# CFD_Timing.net
KiCad netlist of a schematic drawn in Altium Designer
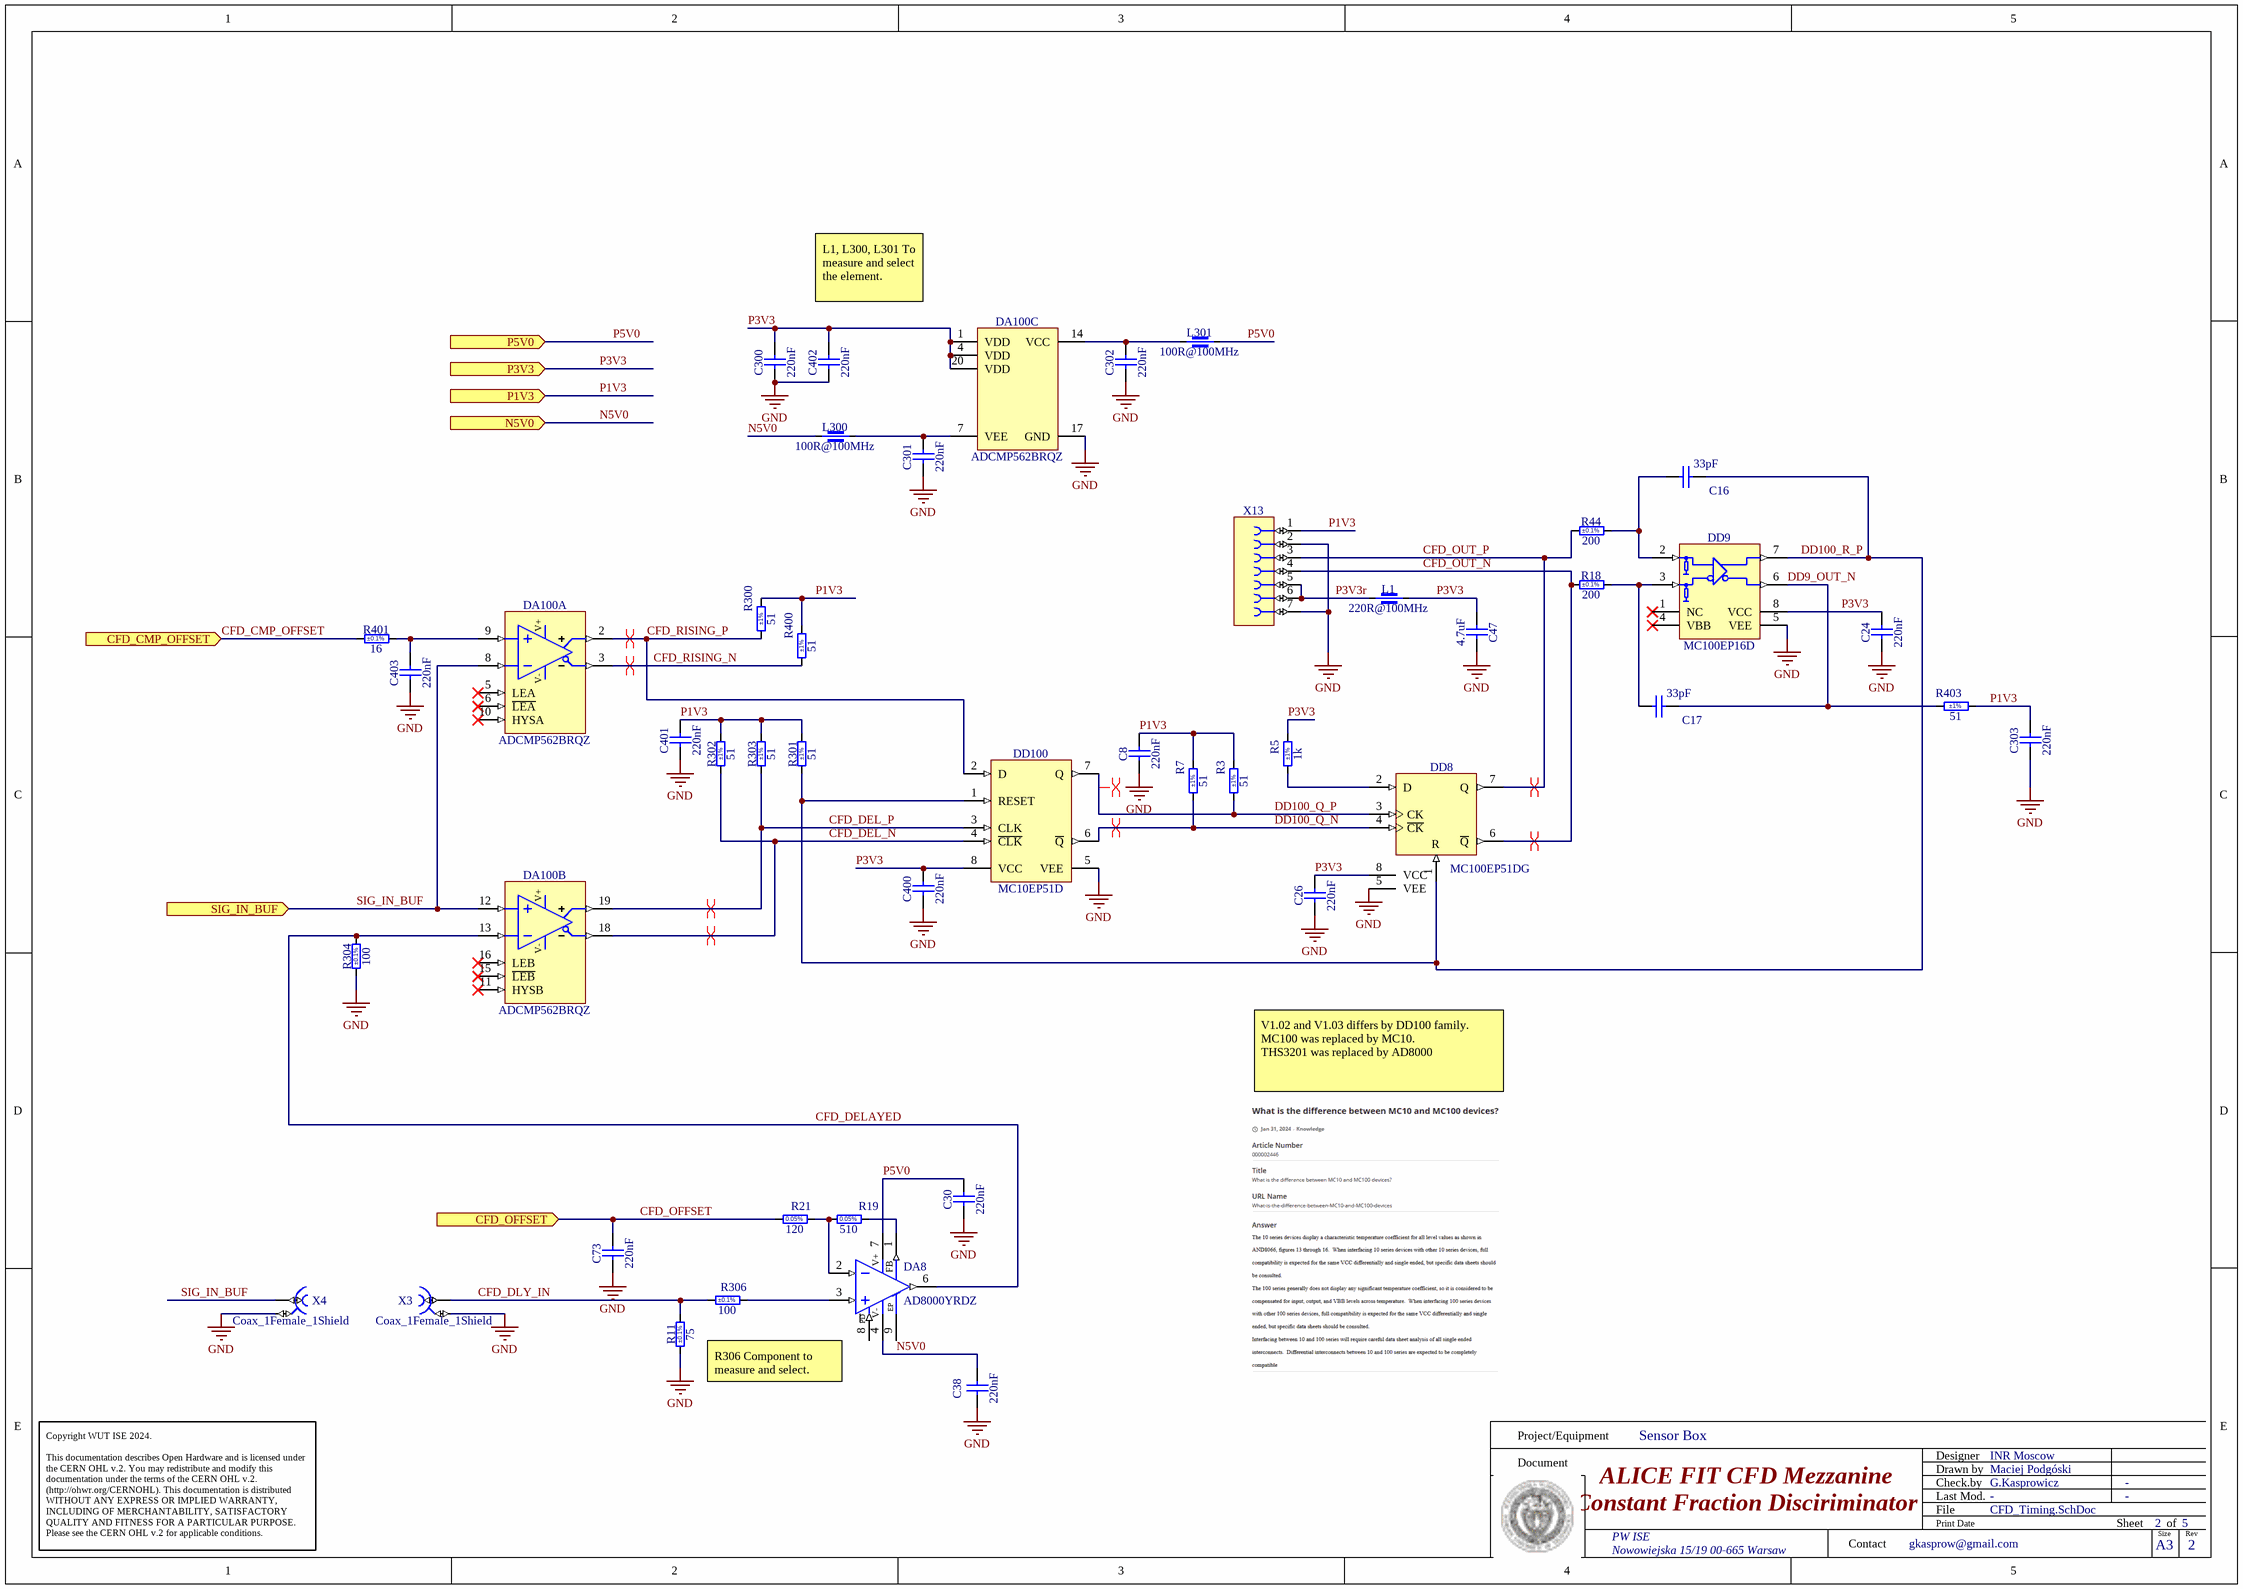
[diagram p0: CFD_Timing.SchDoc]

(export (version "E")
  (design (tool "Eeschema 10.0.6"))
  (components
    (comp (ref "C8")
      (value "220nF")
      (footprint "CAPC2012X135N")
      (description "Non-polarised capacitor")
      (fields
        (field (name "PART NUMBER") "CC0805_220NF_50V_10%_X7R")
        (field (name "VOLTAGE") "50V")
        (field (name "AUTHOR") "CERN DEM JLC")
      )
      (libsource (lib "Capacitors") (part "Capacitor - non polarized"))
    )
    (comp (ref "C16")
      (value "33pF")
      (footprint "CAPC2012X135N")
      (description "Non-polarised capacitor")
      (fields
        (field (name "PART NUMBER") "CC0805_33PF_50V_5%_NP0")
        (field (name "VOLTAGE") "50V")
        (field (name "AUTHOR") "CERN DEM JLC")
      )
      (libsource (lib "Capacitors") (part "Capacitor - non polarized"))
    )
    (comp (ref "C17")
      (value "33pF")
      (footprint "CAPC2012X135N")
      (description "Non-polarised capacitor")
      (fields
        (field (name "PART NUMBER") "CC0805_33PF_50V_5%_NP0")
        (field (name "VOLTAGE") "50V")
        (field (name "AUTHOR") "CERN DEM JLC")
      )
      (libsource (lib "Capacitors") (part "Capacitor - non polarized"))
    )
    (comp (ref "C24")
      (value "220nF")
      (footprint "CAPC2012X135N")
      (description "Non-polarised capacitor")
      (fields
        (field (name "PART NUMBER") "CC0805_220NF_50V_10%_X7R")
        (field (name "VOLTAGE") "50V")
        (field (name "AUTHOR") "CERN DEM JLC")
      )
      (libsource (lib "Capacitors") (part "Capacitor - non polarized"))
    )
    (comp (ref "C26")
      (value "220nF")
      (footprint "CAPC2012X135N")
      (description "Non-polarised capacitor")
      (fields
        (field (name "PART NUMBER") "CC0805_220NF_50V_10%_X7R")
        (field (name "VOLTAGE") "50V")
        (field (name "AUTHOR") "CERN DEM JLC")
      )
      (libsource (lib "Capacitors") (part "Capacitor - non polarized"))
    )
    (comp (ref "C30")
      (value "220nF")
      (footprint "CAPC2012X135N")
      (description "Non-polarised capacitor")
      (fields
        (field (name "PART NUMBER") "CC0805_220NF_50V_10%_X7R")
        (field (name "VOLTAGE") "50V")
        (field (name "AUTHOR") "CERN DEM JLC")
      )
      (libsource (lib "Capacitors") (part "Capacitor - non polarized"))
    )
    (comp (ref "C38")
      (value "220nF")
      (footprint "CAPC2012X135N")
      (description "Non-polarised capacitor")
      (fields
        (field (name "PART NUMBER") "CC0805_220NF_50V_10%_X7R")
        (field (name "VOLTAGE") "50V")
        (field (name "AUTHOR") "CERN DEM JLC")
      )
      (libsource (lib "Capacitors") (part "Capacitor - non polarized"))
    )
    (comp (ref "C47")
      (value "4.7uF")
      (footprint "CAPC3216X180N")
      (description "Non-polarised capacitor")
      (fields
        (field (name "PART NUMBER") "CC1206_4.7UF_25V_10%_X7R")
        (field (name "VOLTAGE") "25V")
        (field (name "AUTHOR") "CERN DEM WB")
      )
      (libsource (lib "Capacitors") (part "Capacitor - non polarized"))
    )
    (comp (ref "C73")
      (value "220nF")
      (footprint "CAPC2012X135N")
      (description "Non-polarised capacitor")
      (fields
        (field (name "PART NUMBER") "CC0805_220NF_50V_10%_X7R")
        (field (name "VOLTAGE") "50V")
        (field (name "AUTHOR") "CERN DEM JLC")
      )
      (libsource (lib "Capacitors") (part "Capacitor - non polarized"))
    )
    (comp (ref "C300")
      (value "220nF")
      (footprint "CAPC1608X87N")
      (description "Non-polarised capacitor")
      (fields
        (field (name "PART NUMBER") "CC0603_220NF_25V_10%_X7R")
        (field (name "VOLTAGE") "25V")
        (field (name "AUTHOR") "CERN DEM JLC")
      )
      (libsource (lib "Capacitors") (part "Capacitor - non polarized"))
    )
    (comp (ref "C301")
      (value "220nF")
      (footprint "CAPC1608X87N")
      (description "Non-polarised capacitor")
      (fields
        (field (name "PART NUMBER") "CC0603_220NF_25V_10%_X7R")
        (field (name "VOLTAGE") "25V")
        (field (name "AUTHOR") "CERN DEM JLC")
      )
      (libsource (lib "Capacitors") (part "Capacitor - non polarized"))
    )
    (comp (ref "C302")
      (value "220nF")
      (footprint "CAPC1608X87N")
      (description "Non-polarised capacitor")
      (fields
        (field (name "PART NUMBER") "CC0603_220NF_25V_10%_X7R")
        (field (name "VOLTAGE") "25V")
        (field (name "AUTHOR") "CERN DEM JLC")
      )
      (libsource (lib "Capacitors") (part "Capacitor - non polarized"))
    )
    (comp (ref "C303")
      (value "220nF")
      (footprint "CAPC2012X135N")
      (description "Non-polarised capacitor")
      (fields
        (field (name "PART NUMBER") "CC0805_220NF_50V_10%_X7R")
        (field (name "VOLTAGE") "50V")
        (field (name "AUTHOR") "CERN DEM JLC")
      )
      (libsource (lib "Capacitors") (part "Capacitor - non polarized"))
    )
    (comp (ref "C400")
      (value "220nF")
      (footprint "CAPC2012X135N")
      (description "Non-polarised capacitor")
      (fields
        (field (name "PART NUMBER") "CC0805_220NF_50V_10%_X7R")
        (field (name "VOLTAGE") "50V")
        (field (name "AUTHOR") "CERN DEM JLC")
      )
      (libsource (lib "Capacitors") (part "Capacitor - non polarized"))
    )
    (comp (ref "C401")
      (value "220nF")
      (footprint "CAPC2012X135N")
      (description "Non-polarised capacitor")
      (fields
        (field (name "PART NUMBER") "CC0805_220NF_50V_10%_X7R")
        (field (name "VOLTAGE") "50V")
        (field (name "AUTHOR") "CERN DEM JLC")
      )
      (libsource (lib "Capacitors") (part "Capacitor - non polarized"))
    )
    (comp (ref "C402")
      (value "220nF")
      (footprint "CAPC1608X87N")
      (description "Non-polarised capacitor")
      (fields
        (field (name "PART NUMBER") "CC0603_220NF_25V_10%_X7R")
        (field (name "VOLTAGE") "25V")
        (field (name "AUTHOR") "CERN DEM JLC")
      )
      (libsource (lib "Capacitors") (part "Capacitor - non polarized"))
    )
    (comp (ref "C403")
      (value "220nF")
      (footprint "CAPC1608X87N")
      (description "Non-polarised capacitor")
      (fields
        (field (name "PART NUMBER") "CC0603_220NF_25V_10%_X7R")
        (field (name "VOLTAGE") "25V")
        (field (name "AUTHOR") "CERN DEM JLC")
      )
      (libsource (lib "Capacitors") (part "Capacitor - non polarized"))
    )
    (comp (ref "DA8")
      (value "AD8000YRDZ")
      (footprint "SOIC127P600X175-9N-S229")
      (description "1.5 GHz Ultrahigh Speed Operational Amplifier")
      (fields
        (field (name "MANUFACTURER") "ANALOG DEVICES")
        (field (name "MANUFACTURER PART NUMBER") "AD8000YRD")
        (field (name "AUTHOR") "CERN DEM JLC")
      )
      (libsource (lib "ICs And Semiconductors") (part "AD8000YRDZ"))
    )
    (comp (ref "DA100")
      (value "ADCMP562BRQZ")
      (footprint "SOP63P600X175-20AN")
      (description "Dual, High Speed PECL Comparators")
      (fields
        (field (name "MANUFACTURER") "ANALOG DEVICES")
        (field (name "MANUFACTURER PART NUMBER") "ADCMP562BRQ")
        (field (name "AUTHOR") "CERN DEM MR")
      )
      (libsource (lib "ICs And Semiconductors") (part "ADCMP562BRQZ"))
    )
    (comp (ref "DD8")
      (value "MC100EP51DG")
      (footprint "SOIC127P600X175-8N")
      (description "3.3V/5V ECL D Flip-Flop with Reset and Differential Clock")
      (fields
        (field (name "MANUFACTURER") "ON SEMICONDUCTOR")
        (field (name "MANUFACTURER PART NUMBER") "MC100EP51D")
        (field (name "AUTHOR") "CERN DEM JLC")
      )
      (libsource (lib "ICs And Semiconductors") (part "100EP51"))
    )
    (comp (ref "DD9")
      (value "MC100EP16D")
      (footprint "SOIC127P600X175-8N")
      (description "3.3V / 5V ECL Differential Receiver/Driver with High Gain")
      (fields (field (name "MANUFACTURER") "ON SEMICONDUCTOR") (field (name "AUTHOR") "CERN DEM HF"))
      (libsource (lib "ICs And Semiconductors") (part "100EP16"))
    )
    (comp (ref "DD100")
      (value "MC10EP51D")
      (footprint "SOP65P490X110-8N")
      (description "3.3V/5V ECL D Flip-Flop with Reset and Differential Clock")
      (fields
        (field (name "PART NUMBER") "MC10EP51DT")
        (field (name "MANUFACTURER") "ON SEMICONDUCTOR")
        (field (name "AUTHOR") "CERN DEM HF")
      )
      (libsource (lib "ICs And Semiconductors") (part "10EP51"))
    )
    (comp (ref "L1")
      (value "220R@100MHz")
      (footprint "INDC2012X105N")
      (fields
        (field (name "PART NUMBER") "IND0805_TDK_MPZ2012S221A")
        (field (name "POWER") "3A")
        (field (name "TOLERANCE") "±25%")
        (field (name "AUTHOR") "CERN DEM HF")
      )
      (libsource (lib "Inductors & Transformers") (part "Ferrite Bead"))
    )
    (comp (ref "L300")
      (value "100R@100MHz")
      (footprint "INDC1608X75N")
      (fields
        (field (name "PART NUMBER") "IND0603_TDK_MPZ1608S101ATAH0")
        (field (name "POWER") "3A")
        (field (name "TOLERANCE") "±25%")
        (field (name "AUTHOR") "CERN DEM JMW")
      )
      (libsource (lib "") (part "Ferrite Bead_1"))
    )
    (comp (ref "L301")
      (value "100R@100MHz")
      (footprint "INDC1608X75N")
      (fields
        (field (name "PART NUMBER") "IND0603_TDK_MPZ1608S101ATAH0")
        (field (name "POWER") "3A")
        (field (name "TOLERANCE") "±25%")
        (field (name "AUTHOR") "CERN DEM JMW")
      )
      (libsource (lib "") (part "Ferrite Bead_1"))
    )
    (comp (ref "R3")
      (value "51")
      (footprint "RESC2012X60N")
      (description "Resistor - 1%")
      (fields
        (field (name "TOLERANCE") "±1%")
        (field (name "PART NUMBER") "R0805_51R_1%_0.125W_100PPM")
        (field (name "POWER") "0.125W")
        (field (name "AUTHOR") "CERN DEM JLC")
      )
      (libsource (lib "Resistors") (part "Resistor - 1%"))
    )
    (comp (ref "R5")
      (value "1k")
      (footprint "RESC2012X60N")
      (description "Resistor - 1%")
      (fields
        (field (name "TOLERANCE") "±1%")
        (field (name "PART NUMBER") "R0805_1K_1%_0.125W_100PPM")
        (field (name "POWER") "0.125W")
        (field (name "AUTHOR") "CERN DEM JLC")
      )
      (libsource (lib "Resistors") (part "Resistor - 1%"))
    )
    (comp (ref "R7")
      (value "51")
      (footprint "RESC2012X60N")
      (description "Resistor - 1%")
      (fields
        (field (name "TOLERANCE") "±1%")
        (field (name "PART NUMBER") "R0805_51R_1%_0.125W_100PPM")
        (field (name "POWER") "0.125W")
        (field (name "AUTHOR") "CERN DEM JLC")
      )
      (libsource (lib "Resistors") (part "Resistor - 1%"))
    )
    (comp (ref "R11")
      (value "75")
      (footprint "RESC1608X55N")
      (description "Resistor - 0.1%")
      (fields
        (field (name "TOLERANCE") "±0.1%")
        (field (name "PART NUMBER") "R0603_75R_0.1%_0.063W_10PPM")
        (field (name "POWER") "0.063W")
        (field (name "AUTHOR") "CERN DEM JLC")
      )
      (libsource (lib "Resistors") (part "Resistor - 0.1%"))
    )
    (comp (ref "R18")
      (value "200")
      (footprint "RESC2012X60N")
      (description "Resistor - 0.1%")
      (fields
        (field (name "TOLERANCE") "±0.1%")
        (field (name "PART NUMBER") "R0805_200R_0.1%_0.1W_10PPM")
        (field (name "POWER") "0.1W")
        (field (name "AUTHOR") "CERN DEM JLC")
      )
      (libsource (lib "Resistors") (part "Resistor - 0.1%"))
    )
    (comp (ref "R19")
      (value "510")
      (footprint "RESC1608X55N")
      (description "Resistor - 0.05%")
      (fields
        (field (name "PART NUMBER") "R0603_510R_0.1%_0.1W_10PPM")
        (field (name "POWER") "0.1W")
        (field (name "AUTHOR") "CERN DEM HF")
      )
      (libsource (lib "Resistors") (part "Resistor - 0.05%"))
    )
    (comp (ref "R21")
      (value "120")
      (footprint "RESC1608X55N")
      (description "Resistor - 0.05%")
      (fields
        (field (name "PART NUMBER") "R0603_120R_0.05%_0.1W_10PPM")
        (field (name "POWER") "0.1W")
        (field (name "AUTHOR") "CERN DEM HF")
      )
      (libsource (lib "Resistors") (part "Resistor - 0.05%"))
    )
    (comp (ref "R44")
      (value "200")
      (footprint "RESC2012X60N")
      (description "Resistor - 0.1%")
      (fields
        (field (name "TOLERANCE") "±0.1%")
        (field (name "PART NUMBER") "R0805_200R_0.1%_0.1W_10PPM")
        (field (name "POWER") "0.1W")
        (field (name "AUTHOR") "CERN DEM JLC")
      )
      (libsource (lib "Resistors") (part "Resistor - 0.1%"))
    )
    (comp (ref "R300")
      (value "51")
      (footprint "RESC2012X60N")
      (description "Resistor - 1%")
      (fields
        (field (name "TOLERANCE") "±1%")
        (field (name "PART NUMBER") "R0805_51R_1%_0.125W_100PPM")
        (field (name "POWER") "0.125W")
        (field (name "AUTHOR") "CERN DEM JLC")
      )
      (libsource (lib "Resistors") (part "Resistor - 1%"))
    )
    (comp (ref "R301")
      (value "51")
      (footprint "RESC2012X60N")
      (description "Resistor - 1%")
      (fields
        (field (name "TOLERANCE") "±1%")
        (field (name "PART NUMBER") "R0805_51R_1%_0.125W_100PPM")
        (field (name "POWER") "0.125W")
        (field (name "AUTHOR") "CERN DEM JLC")
      )
      (libsource (lib "Resistors") (part "Resistor - 1%"))
    )
    (comp (ref "R302")
      (value "51")
      (footprint "RESC2012X60N")
      (description "Resistor - 1%")
      (fields
        (field (name "TOLERANCE") "±1%")
        (field (name "PART NUMBER") "R0805_51R_1%_0.125W_100PPM")
        (field (name "POWER") "0.125W")
        (field (name "AUTHOR") "CERN DEM JLC")
      )
      (libsource (lib "Resistors") (part "Resistor - 1%"))
    )
    (comp (ref "R303")
      (value "51")
      (footprint "RESC2012X60N")
      (description "Resistor - 1%")
      (fields
        (field (name "TOLERANCE") "±1%")
        (field (name "PART NUMBER") "R0805_51R_1%_0.125W_100PPM")
        (field (name "POWER") "0.125W")
        (field (name "AUTHOR") "CERN DEM JLC")
      )
      (libsource (lib "Resistors") (part "Resistor - 1%"))
    )
    (comp (ref "R304")
      (value "100")
      (footprint "RESC1608X55N")
      (description "Resistor - 0.1%")
      (fields
        (field (name "TOLERANCE") "±0.1%")
        (field (name "PART NUMBER") "R0603_100R_0.1%_0.1W_10PPM_VISHAY_MCT")
        (field (name "POWER") "0.1W")
        (field (name "AUTHOR") "CERN DEM BC")
      )
      (libsource (lib "Resistors") (part "Resistor - 0.1%"))
    )
    (comp (ref "R306")
      (value "100")
      (footprint "RESC1005X35N")
      (description "Resistor - 0.1%")
      (fields
        (field (name "TOLERANCE") "±0.1%")
        (field (name "PART NUMBER") "R0402_100R_0.1%_0.063W_25PPM")
        (field (name "POWER") "0.063W")
        (field (name "AUTHOR") "CERN DEM JMW")
      )
      (libsource (lib "Resistors") (part "Resistor - 0.1%"))
    )
    (comp (ref "R400")
      (value "51")
      (footprint "RESC2012X60N")
      (description "Resistor - 1%")
      (fields
        (field (name "TOLERANCE") "±1%")
        (field (name "PART NUMBER") "R0805_51R_1%_0.125W_100PPM")
        (field (name "POWER") "0.125W")
        (field (name "AUTHOR") "CERN DEM JLC")
      )
      (libsource (lib "Resistors") (part "Resistor - 1%"))
    )
    (comp (ref "R401")
      (value "16")
      (footprint "RESC1608X64N")
      (description "Resistor - 0.1%")
      (fields
        (field (name "TOLERANCE") "±0.1%")
        (field (name "PART NUMBER") "R0603_16R_0.1%_0.1W_10PPM")
        (field (name "POWER") "0.1W")
        (field (name "AUTHOR") "CERN DEM HF")
      )
      (libsource (lib "Resistors") (part "Resistor - 0.1%"))
    )
    (comp (ref "R403")
      (value "51")
      (footprint "RESC2012X60N")
      (description "Resistor - 1%")
      (fields
        (field (name "TOLERANCE") "±1%")
        (field (name "PART NUMBER") "R0805_51R_1%_0.125W_100PPM")
        (field (name "POWER") "0.125W")
        (field (name "AUTHOR") "CERN DEM JLC")
      )
      (libsource (lib "Resistors") (part "Resistor - 1%"))
    )
    (comp (ref "X3")
      (value "Coax_1Female_1Shield")
      (footprint "SAMTEC_MMCX-J-P-H-ST-TH1")
      (fields
        (field (name "PART NUMBER") "SAMTEC_MMCX-J-P-H-ST-TH1")
        (field (name "MANUFACTURER") "SAMTEC")
        (field (name "MANUFACTURER PART NUMBER") "MMCX-J-P-H-ST-TH1")
        (field (name "AUTHOR") "CERN DEM JLC")
      )
      (libsource (lib "Connectors") (part "Coax_1Female_1Shield"))
    )
    (comp (ref "X4")
      (value "Coax_1Female_1Shield")
      (footprint "SAMTEC_MMCX-J-P-H-ST-TH1")
      (fields
        (field (name "PART NUMBER") "SAMTEC_MMCX-J-P-H-ST-TH1")
        (field (name "MANUFACTURER") "SAMTEC")
        (field (name "MANUFACTURER PART NUMBER") "MMCX-J-P-H-ST-TH1")
        (field (name "AUTHOR") "CERN DEM JLC")
      )
      (libsource (lib "") (part "Coax_1Female_1Shield_1"))
    )
    (comp (ref "X13")
      (value "Socket 7")
      (footprint "SAMTEC_CES-107-01-T-S")
      (description "Connector 7 Female")
      (fields
        (field (name "PART NUMBER") "SAMTEC_CES-107-01-L-S")
        (field (name "MANUFACTURER") "SAMTEC")
        (field (name "AUTHOR") "CERN DEM HF")
      )
      (libsource (lib "Connectors") (part "Connector 7 Female"))
    )
  )
  (nets
    (net (code "1") (name "/CFD_CMP_OFFSET") (class "Default")
      (node (ref "R401") (pin "1") (pinfunction "1_1") (pintype "passive"))
    )
    (net (code "2") (name "/CFD_DELAYED") (class "Default")
      (node (ref "DA100") (pin "13") (pinfunction "-INB_13") (pintype "input"))
      (node (ref "DA8") (pin "6") (pinfunction "OUT_6") (pintype "output"))
      (node (ref "R304") (pin "2") (pinfunction "2_2") (pintype "passive"))
    )
    (net (code "3") (name "/CFD_DEL_N") (class "Default")
      (node (ref "DA100") (pin "18") (pinfunction "~{QB}_18") (pintype "output"))
      (node (ref "DD100") (pin "4") (pinfunction "~{CLK}_4") (pintype "input"))
      (node (ref "R302") (pin "1") (pinfunction "1_1") (pintype "passive"))
    )
    (net (code "4") (name "/CFD_DEL_P") (class "Default")
      (node (ref "DA100") (pin "19") (pinfunction "QB_19") (pintype "output"))
      (node (ref "DD100") (pin "3") (pinfunction "CLK_3") (pintype "input"))
      (node (ref "R303") (pin "1") (pinfunction "1_1") (pintype "passive"))
    )
    (net (code "5") (name "/CFD_DLY_IN") (class "Default")
      (node (ref "R11") (pin "2") (pinfunction "2_2") (pintype "passive"))
      (node (ref "R306") (pin "1") (pinfunction "1_1") (pintype "passive"))
      (node (ref "X3") (pin "1") (pinfunction "1_1") (pintype "bidirectional"))
    )
    (net (code "6") (name "/CFD_OFFSET") (class "Default")
      (node (ref "C73") (pin "2") (pinfunction "2_2") (pintype "passive"))
      (node (ref "R21") (pin "1") (pinfunction "1_1") (pintype "passive"))
    )
    (net (code "7") (name "/CFD_OUT_N") (class "Default")
      (node (ref "DD8") (pin "6") (pinfunction "~{Q}_6") (pintype "output"))
      (node (ref "R18") (pin "1") (pinfunction "1_1") (pintype "passive"))
      (node (ref "X13") (pin "4") (pinfunction "4_4") (pintype "bidirectional"))
    )
    (net (code "8") (name "/CFD_OUT_P") (class "Default")
      (node (ref "DD8") (pin "7") (pinfunction "Q_7") (pintype "output"))
      (node (ref "R44") (pin "1") (pinfunction "1_1") (pintype "passive"))
      (node (ref "X13") (pin "3") (pinfunction "3_3") (pintype "bidirectional"))
    )
    (net (code "9") (name "/CFD_RISING_N") (class "Default")
      (node (ref "DA100") (pin "3") (pinfunction "~{QA}_3") (pintype "output"))
      (node (ref "R400") (pin "1") (pinfunction "1_1") (pintype "passive"))
    )
    (net (code "10") (name "/CFD_RISING_P") (class "Default")
      (node (ref "DA100") (pin "2") (pinfunction "QA_2") (pintype "output"))
      (node (ref "DD100") (pin "2") (pinfunction "D_2") (pintype "input"))
      (node (ref "R300") (pin "1") (pinfunction "1_1") (pintype "passive"))
    )
    (net (code "11") (name "/DD9_OUT_N") (class "Default")
      (node (ref "C17") (pin "1") (pinfunction "1_1") (pintype "passive"))
      (node (ref "DD9") (pin "6") (pinfunction "~{Q}_6") (pintype "output"))
      (node (ref "R403") (pin "1") (pinfunction "1_1") (pintype "passive"))
    )
    (net (code "12") (name "/DD100_Q_N") (class "Default")
      (node (ref "DD100") (pin "6") (pinfunction "~{Q}_6") (pintype "output"))
      (node (ref "DD8") (pin "4") (pinfunction "~{CK}_4") (pintype "input"))
      (node (ref "R7") (pin "1") (pinfunction "1_1") (pintype "passive"))
    )
    (net (code "13") (name "/DD100_Q_P") (class "Default")
      (node (ref "DD100") (pin "7") (pinfunction "Q_7") (pintype "output"))
      (node (ref "DD8") (pin "3") (pinfunction "CK_3") (pintype "input"))
      (node (ref "R3") (pin "1") (pinfunction "1_1") (pintype "passive"))
    )
    (net (code "14") (name "/DD100_R_P") (class "Default")
      (node (ref "C16") (pin "1") (pinfunction "1_1") (pintype "passive"))
      (node (ref "DD100") (pin "1") (pinfunction "RESET_1") (pintype "input"))
      (node (ref "DD8") (pin "1") (pinfunction "R_1") (pintype "input"))
      (node (ref "DD9") (pin "7") (pinfunction "Q_7") (pintype "output"))
      (node (ref "R301") (pin "1") (pinfunction "1_1") (pintype "passive"))
    )
    (net (code "15") (name "/N5V0") (class "Default")
      (node (ref "C38") (pin "2") (pinfunction "2_2") (pintype "passive"))
      (node (ref "DA8") (pin "4") (pinfunction "V-_4") (pintype "power_in"))
      (node (ref "L300") (pin "1") (pinfunction "1_1") (pintype "passive"))
    )
    (net (code "16") (name "/P1V3") (class "Default")
      (node (ref "C303") (pin "2") (pinfunction "2_2") (pintype "passive"))
      (node (ref "C401") (pin "2") (pinfunction "2_2") (pintype "passive"))
      (node (ref "C8") (pin "2") (pinfunction "2_2") (pintype "passive"))
      (node (ref "R3") (pin "2") (pinfunction "2_2") (pintype "passive"))
      (node (ref "R300") (pin "2") (pinfunction "2_2") (pintype "passive"))
      (node (ref "R301") (pin "2") (pinfunction "2_2") (pintype "passive"))
      (node (ref "R302") (pin "2") (pinfunction "2_2") (pintype "passive"))
      (node (ref "R303") (pin "2") (pinfunction "2_2") (pintype "passive"))
      (node (ref "R400") (pin "2") (pinfunction "2_2") (pintype "passive"))
      (node (ref "R403") (pin "2") (pinfunction "2_2") (pintype "passive"))
      (node (ref "R7") (pin "2") (pinfunction "2_2") (pintype "passive"))
      (node (ref "X13") (pin "1") (pinfunction "1_1") (pintype "bidirectional"))
    )
    (net (code "17") (name "/P3V3") (class "Default")
      (node (ref "C24") (pin "2") (pinfunction "2_2") (pintype "passive"))
      (node (ref "C26") (pin "2") (pinfunction "2_2") (pintype "passive"))
      (node (ref "C300") (pin "2") (pinfunction "2_2") (pintype "passive"))
      (node (ref "C400") (pin "2") (pinfunction "2_2") (pintype "passive"))
      (node (ref "C402") (pin "2") (pinfunction "2_2") (pintype "passive"))
      (node (ref "C47") (pin "2") (pinfunction "2_2") (pintype "passive"))
      (node (ref "DA100") (pin "1") (pinfunction "VDD_1") (pintype "power_in"))
      (node (ref "DA100") (pin "20") (pinfunction "VDD_20") (pintype "power_in"))
      (node (ref "DA100") (pin "4") (pinfunction "VDD_4") (pintype "power_in"))
      (node (ref "DD100") (pin "8") (pinfunction "VCC_8") (pintype "power_in"))
      (node (ref "DD8") (pin "8") (pinfunction "VCC_8") (pintype "power_in"))
      (node (ref "DD9") (pin "8") (pinfunction "VCC_8") (pintype "power_in"))
      (node (ref "L1") (pin "1") (pinfunction "1_1") (pintype "passive"))
      (node (ref "R5") (pin "2") (pinfunction "2_2") (pintype "passive"))
    )
    (net (code "18") (name "/P3V3r") (class "Default")
      (node (ref "L1") (pin "2") (pinfunction "2_2") (pintype "passive"))
      (node (ref "X13") (pin "5") (pinfunction "5_5") (pintype "bidirectional"))
      (node (ref "X13") (pin "6") (pinfunction "6_6") (pintype "bidirectional"))
    )
    (net (code "19") (name "/P5V0") (class "Default")
      (node (ref "C30") (pin "2") (pinfunction "2_2") (pintype "passive"))
      (node (ref "DA8") (pin "7") (pinfunction "V+_7") (pintype "power_in"))
      (node (ref "L301") (pin "2") (pinfunction "2_2") (pintype "passive"))
    )
    (net (code "20") (name "/SIG_IN_BUF") (class "Default")
      (node (ref "DA100") (pin "12") (pinfunction "+INB_12") (pintype "input"))
      (node (ref "DA100") (pin "8") (pinfunction "-INA_8") (pintype "input"))
      (node (ref "X4") (pin "1") (pinfunction "1_1") (pintype "bidirectional"))
    )
    (net (code "21") (name "GND") (class "Default")
      (node (ref "C24") (pin "1") (pinfunction "1_1") (pintype "passive"))
      (node (ref "C26") (pin "1") (pinfunction "1_1") (pintype "passive"))
      (node (ref "C30") (pin "1") (pinfunction "1_1") (pintype "passive"))
      (node (ref "C300") (pin "1") (pinfunction "1_1") (pintype "passive"))
      (node (ref "C301") (pin "1") (pinfunction "1_1") (pintype "passive"))
      (node (ref "C302") (pin "1") (pinfunction "1_1") (pintype "passive"))
      (node (ref "C303") (pin "1") (pinfunction "1_1") (pintype "passive"))
      (node (ref "C38") (pin "1") (pinfunction "1_1") (pintype "passive"))
      (node (ref "C400") (pin "1") (pinfunction "1_1") (pintype "passive"))
      (node (ref "C401") (pin "1") (pinfunction "1_1") (pintype "passive"))
      (node (ref "C402") (pin "1") (pinfunction "1_1") (pintype "passive"))
      (node (ref "C403") (pin "1") (pinfunction "1_1") (pintype "passive"))
      (node (ref "C47") (pin "1") (pinfunction "1_1") (pintype "passive"))
      (node (ref "C73") (pin "1") (pinfunction "1_1") (pintype "passive"))
      (node (ref "C8") (pin "1") (pinfunction "1_1") (pintype "passive"))
      (node (ref "DA100") (pin "17") (pinfunction "GND_17") (pintype "power_in"))
      (node (ref "DD100") (pin "5") (pinfunction "VEE_5") (pintype "power_in"))
      (node (ref "DD8") (pin "5") (pinfunction "VEE_5") (pintype "power_in"))
      (node (ref "DD9") (pin "5") (pinfunction "VEE_5") (pintype "power_in"))
      (node (ref "R11") (pin "1") (pinfunction "1_1") (pintype "passive"))
      (node (ref "R304") (pin "1") (pinfunction "1_1") (pintype "passive"))
      (node (ref "X13") (pin "2") (pinfunction "2_2") (pintype "bidirectional"))
      (node (ref "X13") (pin "7") (pinfunction "7_7") (pintype "bidirectional"))
      (node (ref "X3") (pin "2") (pinfunction "2_2") (pintype "bidirectional"))
      (node (ref "X4") (pin "2") (pinfunction "2_2") (pintype "bidirectional"))
    )
    (net (code "22") (name "Net-(DA8-FB)") (class "Default")
      (node (ref "DA8") (pin "1") (pinfunction "FB_1") (pintype "output"))
      (node (ref "R19") (pin "2") (pinfunction "2_2") (pintype "passive"))
    )
    (net (code "23") (name "Net-(DA8-IN+)") (class "Default")
      (node (ref "DA8") (pin "3") (pinfunction "IN+_3") (pintype "input"))
      (node (ref "R306") (pin "2") (pinfunction "2_2") (pintype "passive"))
    )
    (net (code "24") (name "Net-(DA8-IN-)") (class "Default")
      (node (ref "DA8") (pin "2") (pinfunction "IN-_2") (pintype "input"))
      (node (ref "R19") (pin "1") (pinfunction "1_1") (pintype "passive"))
      (node (ref "R21") (pin "2") (pinfunction "2_2") (pintype "passive"))
    )
    (net (code "25") (name "Net-(DA100A-+INA)") (class "Default")
      (node (ref "C403") (pin "2") (pinfunction "2_2") (pintype "passive"))
      (node (ref "DA100") (pin "9") (pinfunction "+INA_9") (pintype "input"))
      (node (ref "R401") (pin "2") (pinfunction "2_2") (pintype "passive"))
    )
    (net (code "26") (name "Net-(DA100C-VCC)") (class "Default")
      (node (ref "C302") (pin "2") (pinfunction "2_2") (pintype "passive"))
      (node (ref "DA100") (pin "14") (pinfunction "VCC_14") (pintype "power_in"))
      (node (ref "L301") (pin "1") (pinfunction "1_1") (pintype "passive"))
    )
    (net (code "27") (name "Net-(DA100C-VEE)") (class "Default")
      (node (ref "C301") (pin "2") (pinfunction "2_2") (pintype "passive"))
      (node (ref "DA100") (pin "7") (pinfunction "VEE_7") (pintype "power_in"))
      (node (ref "L300") (pin "2") (pinfunction "2_2") (pintype "passive"))
    )
    (net (code "28") (name "Net-(DD8-D)") (class "Default")
      (node (ref "DD8") (pin "2") (pinfunction "D_2") (pintype "input"))
      (node (ref "R5") (pin "1") (pinfunction "1_1") (pintype "passive"))
    )
    (net (code "29") (name "Net-(DD9-D0)") (class "Default")
      (node (ref "C16") (pin "2") (pinfunction "2_2") (pintype "passive"))
      (node (ref "DD9") (pin "2") (pinfunction "D0_2") (pintype "input"))
      (node (ref "R44") (pin "2") (pinfunction "2_2") (pintype "passive"))
    )
    (net (code "30") (name "Net-(DD9-~{D0})") (class "Default")
      (node (ref "C17") (pin "2") (pinfunction "2_2") (pintype "passive"))
      (node (ref "DD9") (pin "3") (pinfunction "~{D0}_3") (pintype "input"))
      (node (ref "R18") (pin "2") (pinfunction "2_2") (pintype "passive"))
    )
    (net (code "31") (name "unconnected-(DA8-EP-Pad9)") (class "Default")
      (node (ref "DA8") (pin "9") (pinfunction "EP_9") (pintype "power_in"))
    )
    (net (code "32") (name "unconnected-(DA8-~{DS}-Pad8)") (class "Default")
      (node (ref "DA8") (pin "8") (pinfunction "~{DS}_8") (pintype "input"))
    )
    (net (code "33") (name "unconnected-(DA100A-HYSA-Pad10)") (class "Default")
      (node (ref "DA100") (pin "10") (pinfunction "HYSA_10") (pintype "input+no_connect"))
    )
    (net (code "34") (name "unconnected-(DA100A-LEA-Pad5)") (class "Default")
      (node (ref "DA100") (pin "5") (pinfunction "LEA_5") (pintype "input+no_connect"))
    )
    (net (code "35") (name "unconnected-(DA100A-~{LEA}-Pad6)") (class "Default")
      (node (ref "DA100") (pin "6") (pinfunction "~{LEA}_6") (pintype "input+no_connect"))
    )
    (net (code "36") (name "unconnected-(DA100B-HYSB-Pad11)") (class "Default")
      (node (ref "DA100") (pin "11") (pinfunction "HYSB_11") (pintype "input+no_connect"))
    )
    (net (code "37") (name "unconnected-(DA100B-LEB-Pad16)") (class "Default")
      (node (ref "DA100") (pin "16") (pinfunction "LEB_16") (pintype "input+no_connect"))
    )
    (net (code "38") (name "unconnected-(DA100B-~{LEB}-Pad15)") (class "Default")
      (node (ref "DA100") (pin "15") (pinfunction "~{LEB}_15") (pintype "input+no_connect"))
    )
    (net (code "39") (name "unconnected-(DD9-NC-Pad1)") (class "Default")
      (node (ref "DD9") (pin "1") (pinfunction "NC_1") (pintype "passive+no_connect"))
    )
    (net (code "40") (name "unconnected-(DD9-VBB-Pad4)") (class "Default")
      (node (ref "DD9") (pin "4") (pinfunction "VBB_4") (pintype "power_in+no_connect"))
    )
  )
)
